# SCH_L2-P2_3.net
KiCad netlist of a schematic drawn in Altium Designer
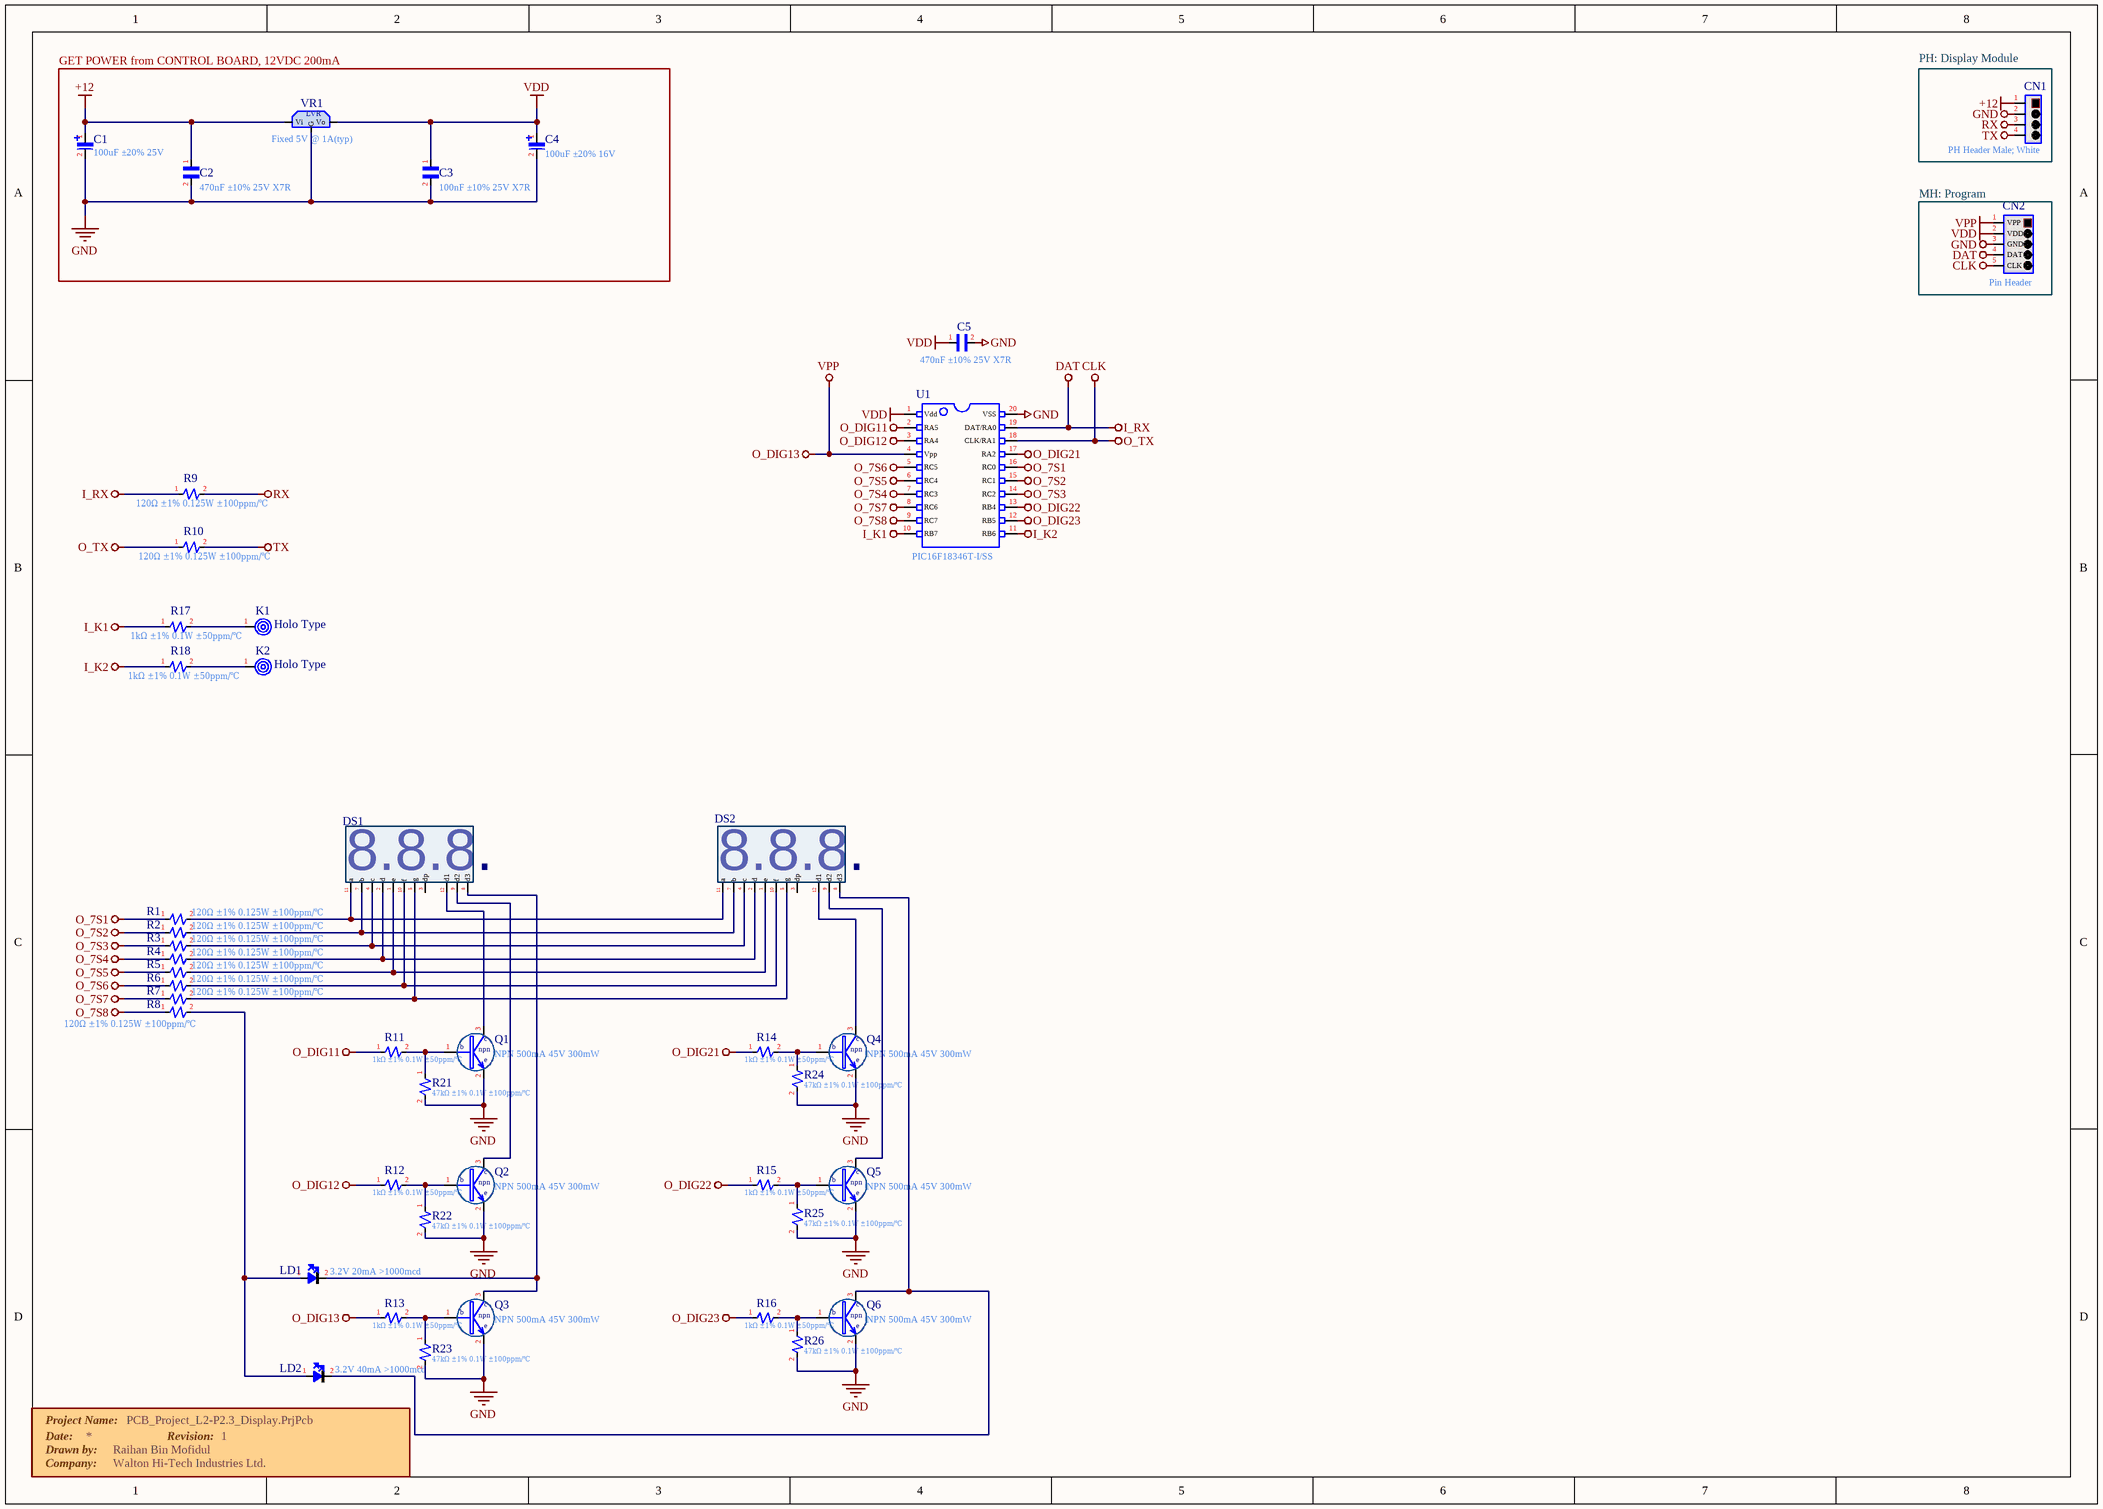
[diagram p0: SCH_L2-P2.3.SchDoc]

(export (version "E")
  (design (tool "Eeschema 10.0.6"))
  (components
    (comp (ref "C1")
      (value "100uF ±20% 25V")
      (footprint "C_SMD_Ø6.3*5.4mm")
      (description "SMD,6.3x5.4mm Aluminum Electrolytic Capacitors - SMD RoHS")
      (libsource (lib "RBM_ALTIUM_SCH_LIBRARY") (part "Capacitor{gt}{gt} Polar"))
    )
    (comp (ref "C2")
      (value "470nF ±10% 25V X7R")
      (footprint "C_0603")
      (description "0603 Multilayer Ceramic Capacitors MLCC - SMD/SMT RoHS")
      (libsource (lib "") (part "Capacitor{gt}{gt} Non-Polar_1"))
    )
    (comp (ref "C3")
      (value "100nF ±10% 25V X7R")
      (footprint "C_0603")
      (description "0603 Multilayer Ceramic Capacitors MLCC - SMD/SMT RoHS")
      (libsource (lib "") (part "Capacitor{gt}{gt} Non-Polar_1"))
    )
    (comp (ref "C4")
      (value "100uF ±20% 16V")
      (footprint "C_SMD_Ø6.3*5.4mm")
      (description "SMD,6.3x5.4mm Aluminum Electrolytic Capacitors - SMD RoHS")
      (libsource (lib "RBM_ALTIUM_SCH_LIBRARY") (part "Capacitor{gt}{gt} Polar"))
    )
    (comp (ref "C5")
      (value "470nF ±10% 25V X7R")
      (footprint "C_0603")
      (description "0603 Multilayer Ceramic Capacitors MLCC - SMD/SMT RoHS")
      (libsource (lib "RBM_ALTIUM_SCH_LIBRARY") (part "Capacitor{gt}{gt} Non-Polar"))
    )
    (comp (ref "CN1")
      (value "PH Header Male; White")
      (footprint "CN_4P_A2001WR-S-XP-LCP")
      (description "A2001WR-S-4P; Pin 0.079\"(2.00mm) 4 SMD,P=2mm Wire To Board / Wire To Wire Connector RoHS")
      (libsource (lib "RBM_ALTIUM_SCH_LIBRARY") (part "Connector{gt}{gt} 4Pins"))
    )
    (comp (ref "CN2")
      (value "Pin Header")
      (footprint "CN_PIC_MCU_Debugger_RightAngle")
      (libsource (lib "RBM_ALTIUM_SCH_LIBRARY") (part "Connector{gt}{gt} PIC Program"))
    )
    (comp (ref "DS1")
      (value "Display>> 7Seg 3Dig")
      (footprint "DS_0.36\"_3DIG")
      (libsource (lib "RBM_ALTIUM_SCH_LIBRARY") (part "Display{gt}{gt} 7Seg 3Dig"))
    )
    (comp (ref "DS2")
      (value "Display>> 7Seg 3Dig")
      (footprint "DS_0.36\"_3DIG")
      (libsource (lib "RBM_ALTIUM_SCH_LIBRARY") (part "Display{gt}{gt} 7Seg 3Dig"))
    )
    (comp (ref "K1")
      (value "Holo Type")
      (footprint "K_Cap-Touch-Square_LED")
      (libsource (lib "RBM_ALTIUM_SCH_LIBRARY") (part "Key{gt}{gt} Cap Touch"))
    )
    (comp (ref "K2")
      (value "Holo Type")
      (footprint "K_Cap-Touch-Square_LED")
      (libsource (lib "RBM_ALTIUM_SCH_LIBRARY") (part "Key{gt}{gt} Cap Touch"))
    )
    (comp (ref "LD1")
      (value "3.2V 20mA >1000mcd")
      (footprint "LED_4.8x5.8_P2.54")
      (libsource (lib "RBM_ALTIUM_SCH_LIBRARY") (part "LED{gt}{gt} General Purpose"))
    )
    (comp (ref "LD2")
      (value "3.2V 40mA >1000mcd")
      (footprint "LED_4.8x5.8_P2.54")
      (libsource (lib "RBM_ALTIUM_SCH_LIBRARY") (part "LED{gt}{gt} General Purpose"))
    )
    (comp (ref "Q1")
      (value "NPN 500mA 45V 300mW")
      (footprint "Q_SOT-23_NPN")
      (description "BC817-40; SOT-23(SOT-23-3) Transistors (NPN/PNP) RoHS")
      (libsource (lib "RBM_ALTIUM_SCH_LIBRARY") (part "Transistor{gt}{gt} BJT npn"))
    )
    (comp (ref "Q2")
      (value "NPN 500mA 45V 300mW")
      (footprint "Q_SOT-23_NPN")
      (description "BC817-40; SOT-23(SOT-23-3) Transistors (NPN/PNP) RoHS")
      (libsource (lib "RBM_ALTIUM_SCH_LIBRARY") (part "Transistor{gt}{gt} BJT npn"))
    )
    (comp (ref "Q3")
      (value "NPN 500mA 45V 300mW")
      (footprint "Q_SOT-23_NPN")
      (description "BC817-40; SOT-23(SOT-23-3) Transistors (NPN/PNP) RoHS")
      (libsource (lib "RBM_ALTIUM_SCH_LIBRARY") (part "Transistor{gt}{gt} BJT npn"))
    )
    (comp (ref "Q4")
      (value "NPN 500mA 45V 300mW")
      (footprint "Q_SOT-23_NPN")
      (description "BC817-40; SOT-23(SOT-23-3) Transistors (NPN/PNP) RoHS")
      (libsource (lib "RBM_ALTIUM_SCH_LIBRARY") (part "Transistor{gt}{gt} BJT npn"))
    )
    (comp (ref "Q5")
      (value "NPN 500mA 45V 300mW")
      (footprint "Q_SOT-23_NPN")
      (description "BC817-40; SOT-23(SOT-23-3) Transistors (NPN/PNP) RoHS")
      (libsource (lib "RBM_ALTIUM_SCH_LIBRARY") (part "Transistor{gt}{gt} BJT npn"))
    )
    (comp (ref "Q6")
      (value "NPN 500mA 45V 300mW")
      (footprint "Q_SOT-23_NPN")
      (description "BC817-40; SOT-23(SOT-23-3) Transistors (NPN/PNP) RoHS")
      (libsource (lib "RBM_ALTIUM_SCH_LIBRARY") (part "Transistor{gt}{gt} BJT npn"))
    )
    (comp (ref "R1")
      (value "120Ω ±1% 0.125W ±100ppm/℃")
      (footprint "R_0603")
      (description "RK73H1JTTD1200F; 0603 Chip Resistor - Surface Mount RoHS")
      (libsource (lib "RBM_ALTIUM_SCH_LIBRARY") (part "Resistor{gt}{gt} General Purpose"))
    )
    (comp (ref "R2")
      (value "120Ω ±1% 0.125W ±100ppm/℃")
      (footprint "R_0603")
      (description "RK73H1JTTD1200F; 0603 Chip Resistor - Surface Mount RoHS")
      (libsource (lib "RBM_ALTIUM_SCH_LIBRARY") (part "Resistor{gt}{gt} General Purpose"))
    )
    (comp (ref "R3")
      (value "120Ω ±1% 0.125W ±100ppm/℃")
      (footprint "R_0603")
      (description "RK73H1JTTD1200F; 0603 Chip Resistor - Surface Mount RoHS")
      (libsource (lib "RBM_ALTIUM_SCH_LIBRARY") (part "Resistor{gt}{gt} General Purpose"))
    )
    (comp (ref "R4")
      (value "120Ω ±1% 0.125W ±100ppm/℃")
      (footprint "R_0603")
      (description "RK73H1JTTD1200F; 0603 Chip Resistor - Surface Mount RoHS")
      (libsource (lib "RBM_ALTIUM_SCH_LIBRARY") (part "Resistor{gt}{gt} General Purpose"))
    )
    (comp (ref "R5")
      (value "120Ω ±1% 0.125W ±100ppm/℃")
      (footprint "R_0603")
      (description "RK73H1JTTD1200F; 0603 Chip Resistor - Surface Mount RoHS")
      (libsource (lib "RBM_ALTIUM_SCH_LIBRARY") (part "Resistor{gt}{gt} General Purpose"))
    )
    (comp (ref "R6")
      (value "120Ω ±1% 0.125W ±100ppm/℃")
      (footprint "R_0603")
      (description "RK73H1JTTD1200F; 0603 Chip Resistor - Surface Mount RoHS")
      (libsource (lib "RBM_ALTIUM_SCH_LIBRARY") (part "Resistor{gt}{gt} General Purpose"))
    )
    (comp (ref "R7")
      (value "120Ω ±1% 0.125W ±100ppm/℃")
      (footprint "R_0603")
      (description "RK73H1JTTD1200F; 0603 Chip Resistor - Surface Mount RoHS")
      (libsource (lib "RBM_ALTIUM_SCH_LIBRARY") (part "Resistor{gt}{gt} General Purpose"))
    )
    (comp (ref "R8")
      (value "120Ω ±1% 0.125W ±100ppm/℃")
      (footprint "R_0603")
      (description "RK73H1JTTD1200F; 0603 Chip Resistor - Surface Mount RoHS")
      (libsource (lib "RBM_ALTIUM_SCH_LIBRARY") (part "Resistor{gt}{gt} General Purpose"))
    )
    (comp (ref "R9")
      (value "120Ω ±1% 0.125W ±100ppm/℃")
      (footprint "R_0603")
      (description "RK73H1JTTD1200F; 0603 Chip Resistor - Surface Mount RoHS")
      (libsource (lib "RBM_ALTIUM_SCH_LIBRARY") (part "Resistor{gt}{gt} General Purpose"))
    )
    (comp (ref "R10")
      (value "120Ω ±1% 0.125W ±100ppm/℃")
      (footprint "R_0603")
      (description "RK73H1JTTD1200F; 0603 Chip Resistor - Surface Mount RoHS")
      (libsource (lib "RBM_ALTIUM_SCH_LIBRARY") (part "Resistor{gt}{gt} General Purpose"))
    )
    (comp (ref "R11")
      (value "1kΩ ±1% 0.1W ±50ppm/℃")
      (footprint "R_0603")
      (description "RK73G1JTTD1001F; 0603 Chip Resistor - Surface Mount RoHS")
      (libsource (lib "RBM_ALTIUM_SCH_LIBRARY") (part "Resistor{gt}{gt} General Purpose"))
    )
    (comp (ref "R12")
      (value "1kΩ ±1% 0.1W ±50ppm/℃")
      (footprint "R_0603")
      (description "RK73G1JTTD1001F; 0603 Chip Resistor - Surface Mount RoHS")
      (libsource (lib "RBM_ALTIUM_SCH_LIBRARY") (part "Resistor{gt}{gt} General Purpose"))
    )
    (comp (ref "R13")
      (value "1kΩ ±1% 0.1W ±50ppm/℃")
      (footprint "R_0603")
      (description "RK73G1JTTD1001F; 0603 Chip Resistor - Surface Mount RoHS")
      (libsource (lib "RBM_ALTIUM_SCH_LIBRARY") (part "Resistor{gt}{gt} General Purpose"))
    )
    (comp (ref "R14")
      (value "1kΩ ±1% 0.1W ±50ppm/℃")
      (footprint "R_0603")
      (description "RK73G1JTTD1001F; 0603 Chip Resistor - Surface Mount RoHS")
      (libsource (lib "RBM_ALTIUM_SCH_LIBRARY") (part "Resistor{gt}{gt} General Purpose"))
    )
    (comp (ref "R15")
      (value "1kΩ ±1% 0.1W ±50ppm/℃")
      (footprint "R_0603")
      (description "RK73G1JTTD1001F; 0603 Chip Resistor - Surface Mount RoHS")
      (libsource (lib "RBM_ALTIUM_SCH_LIBRARY") (part "Resistor{gt}{gt} General Purpose"))
    )
    (comp (ref "R16")
      (value "1kΩ ±1% 0.1W ±50ppm/℃")
      (footprint "R_0603")
      (description "RK73G1JTTD1001F; 0603 Chip Resistor - Surface Mount RoHS")
      (libsource (lib "RBM_ALTIUM_SCH_LIBRARY") (part "Resistor{gt}{gt} General Purpose"))
    )
    (comp (ref "R17")
      (value "1kΩ ±1% 0.1W ±50ppm/℃")
      (footprint "R_0603")
      (description "RK73G1JTTD1001F; 0603 Chip Resistor - Surface Mount RoHS")
      (libsource (lib "RBM_ALTIUM_SCH_LIBRARY") (part "Resistor{gt}{gt} General Purpose"))
    )
    (comp (ref "R18")
      (value "1kΩ ±1% 0.1W ±50ppm/℃")
      (footprint "R_0603")
      (description "RK73G1JTTD1001F; 0603 Chip Resistor - Surface Mount RoHS")
      (libsource (lib "RBM_ALTIUM_SCH_LIBRARY") (part "Resistor{gt}{gt} General Purpose"))
    )
    (comp (ref "R21")
      (value "47kΩ ±1% 0.1W ±100ppm/℃")
      (footprint "R_0603")
      (description "RK73H1JTTD4702F; 0603 Chip Resistor - Surface Mount RoHS")
      (libsource (lib "RBM_ALTIUM_SCH_LIBRARY") (part "Resistor{gt}{gt} General Purpose"))
    )
    (comp (ref "R22")
      (value "47kΩ ±1% 0.1W ±100ppm/℃")
      (footprint "R_0603")
      (description "RK73H1JTTD4702F; 0603 Chip Resistor - Surface Mount RoHS")
      (libsource (lib "RBM_ALTIUM_SCH_LIBRARY") (part "Resistor{gt}{gt} General Purpose"))
    )
    (comp (ref "R23")
      (value "47kΩ ±1% 0.1W ±100ppm/℃")
      (footprint "R_0603")
      (description "RK73H1JTTD4702F; 0603 Chip Resistor - Surface Mount RoHS")
      (libsource (lib "RBM_ALTIUM_SCH_LIBRARY") (part "Resistor{gt}{gt} General Purpose"))
    )
    (comp (ref "R24")
      (value "47kΩ ±1% 0.1W ±100ppm/℃")
      (footprint "R_0603")
      (description "RK73H1JTTD4702F; 0603 Chip Resistor - Surface Mount RoHS")
      (libsource (lib "RBM_ALTIUM_SCH_LIBRARY") (part "Resistor{gt}{gt} General Purpose"))
    )
    (comp (ref "R25")
      (value "47kΩ ±1% 0.1W ±100ppm/℃")
      (footprint "R_0603")
      (description "RK73H1JTTD4702F; 0603 Chip Resistor - Surface Mount RoHS")
      (libsource (lib "RBM_ALTIUM_SCH_LIBRARY") (part "Resistor{gt}{gt} General Purpose"))
    )
    (comp (ref "R26")
      (value "47kΩ ±1% 0.1W ±100ppm/℃")
      (footprint "R_0603")
      (description "RK73H1JTTD4702F; 0603 Chip Resistor - Surface Mount RoHS")
      (libsource (lib "RBM_ALTIUM_SCH_LIBRARY") (part "Resistor{gt}{gt} General Purpose"))
    )
    (comp (ref "U1")
      (value "PIC16F18346T-I/SS")
      (footprint "U_PIC_20pin_SSOP")
      (libsource (lib "RBM_ALTIUM_SCH_LIBRARY") (part "IC{gt}{gt} PIC 20Pins"))
    )
    (comp (ref "VR1")
      (value "Fixed 5V @ 1A(typ)")
      (footprint "VR_TO-252-2(DPAK)")
      (description "CJ78D05/MC7805BDTRKG; TO-252-2(DPAK) Dropout Regulators(LDO) RoHS")
      (libsource (lib "RBM_ALTIUM_SCH_LIBRARY") (part "Voltage Regulator"))
    )
  )
  (nets
    (net (code "1") (name "+12") (class "Default")
      (node (ref "C1") (pin "1") (pinfunction "1_1") (pintype "passive"))
      (node (ref "C2") (pin "1") (pinfunction "1_1") (pintype "passive"))
      (node (ref "CN1") (pin "1") (pinfunction "1_1") (pintype "passive"))
      (node (ref "VR1") (pin "V-IN") (pinfunction "Vi_V-IN") (pintype "passive"))
    )
    (net (code "2") (name "CLK") (class "Default")
      (node (ref "CN2") (pin "5") (pinfunction "CLK_5") (pintype "passive"))
      (node (ref "R10") (pin "1") (pinfunction "1_1") (pintype "passive"))
      (node (ref "U1") (pin "18") (pinfunction "CLK/RA1_18") (pintype "passive"))
    )
    (net (code "3") (name "DAT") (class "Default")
      (node (ref "CN2") (pin "4") (pinfunction "DAT_4") (pintype "passive"))
      (node (ref "R9") (pin "1") (pinfunction "1_1") (pintype "passive"))
      (node (ref "U1") (pin "19") (pinfunction "DAT/RA0_19") (pintype "passive"))
    )
    (net (code "4") (name "GND") (class "Default")
      (node (ref "C1") (pin "2") (pinfunction "2_2") (pintype "passive"))
      (node (ref "C2") (pin "2") (pinfunction "2_2") (pintype "passive"))
      (node (ref "C3") (pin "2") (pinfunction "2_2") (pintype "passive"))
      (node (ref "C4") (pin "2") (pinfunction "2_2") (pintype "passive"))
      (node (ref "C5") (pin "2") (pinfunction "2_2") (pintype "passive"))
      (node (ref "CN1") (pin "2") (pinfunction "2_2") (pintype "passive"))
      (node (ref "CN2") (pin "3") (pinfunction "GND_3") (pintype "passive"))
      (node (ref "Q1") (pin "2") (pinfunction "Emitter_2") (pintype "passive"))
      (node (ref "Q2") (pin "2") (pinfunction "Emitter_2") (pintype "passive"))
      (node (ref "Q3") (pin "2") (pinfunction "Emitter_2") (pintype "passive"))
      (node (ref "Q4") (pin "2") (pinfunction "Emitter_2") (pintype "passive"))
      (node (ref "Q5") (pin "2") (pinfunction "Emitter_2") (pintype "passive"))
      (node (ref "Q6") (pin "2") (pinfunction "Emitter_2") (pintype "passive"))
      (node (ref "R21") (pin "2") (pinfunction "2_2") (pintype "passive"))
      (node (ref "R22") (pin "2") (pinfunction "2_2") (pintype "passive"))
      (node (ref "R23") (pin "2") (pinfunction "2_2") (pintype "passive"))
      (node (ref "R24") (pin "2") (pinfunction "2_2") (pintype "passive"))
      (node (ref "R25") (pin "2") (pinfunction "2_2") (pintype "passive"))
      (node (ref "R26") (pin "2") (pinfunction "2_2") (pintype "passive"))
      (node (ref "U1") (pin "20") (pinfunction "VSS_20") (pintype "passive"))
      (node (ref "VR1") (pin "GND") (pinfunction "G_GND") (pintype "passive"))
    )
    (net (code "5") (name "I_K1") (class "Default")
      (node (ref "R17") (pin "1") (pinfunction "1_1") (pintype "passive"))
      (node (ref "U1") (pin "10") (pinfunction "RB7_10") (pintype "passive"))
    )
    (net (code "6") (name "I_K2") (class "Default")
      (node (ref "R18") (pin "1") (pinfunction "1_1") (pintype "passive"))
      (node (ref "U1") (pin "11") (pinfunction "RB6_11") (pintype "passive"))
    )
    (net (code "7") (name "Net-(DS1-a)") (class "Default")
      (node (ref "DS1") (pin "11") (pinfunction "a_11") (pintype "passive"))
      (node (ref "DS2") (pin "11") (pinfunction "a_11") (pintype "passive"))
      (node (ref "R1") (pin "2") (pinfunction "2_2") (pintype "passive"))
    )
    (net (code "8") (name "Net-(DS1-b)") (class "Default")
      (node (ref "DS1") (pin "7") (pinfunction "b_7") (pintype "passive"))
      (node (ref "DS2") (pin "7") (pinfunction "b_7") (pintype "passive"))
      (node (ref "R2") (pin "2") (pinfunction "2_2") (pintype "passive"))
    )
    (net (code "9") (name "Net-(DS1-c)") (class "Default")
      (node (ref "DS1") (pin "4") (pinfunction "c_4") (pintype "passive"))
      (node (ref "DS2") (pin "4") (pinfunction "c_4") (pintype "passive"))
      (node (ref "R3") (pin "2") (pinfunction "2_2") (pintype "passive"))
    )
    (net (code "10") (name "Net-(DS1-d)") (class "Default")
      (node (ref "DS1") (pin "2") (pinfunction "d_2") (pintype "passive"))
      (node (ref "DS2") (pin "2") (pinfunction "d_2") (pintype "passive"))
      (node (ref "R4") (pin "2") (pinfunction "2_2") (pintype "passive"))
    )
    (net (code "11") (name "Net-(DS1-d1)") (class "Default")
      (node (ref "DS1") (pin "12") (pinfunction "d1_12") (pintype "passive"))
      (node (ref "Q1") (pin "3") (pinfunction "Collector_3") (pintype "passive"))
    )
    (net (code "12") (name "Net-(DS1-d2)") (class "Default")
      (node (ref "DS1") (pin "9") (pinfunction "d2_9") (pintype "passive"))
      (node (ref "Q2") (pin "3") (pinfunction "Collector_3") (pintype "passive"))
    )
    (net (code "13") (name "Net-(DS1-d3)") (class "Default")
      (node (ref "DS1") (pin "8") (pinfunction "d3_8") (pintype "passive"))
      (node (ref "LD1") (pin "2") (pinfunction "vss_2") (pintype "passive"))
      (node (ref "Q3") (pin "3") (pinfunction "Collector_3") (pintype "passive"))
    )
    (net (code "14") (name "Net-(DS1-e)") (class "Default")
      (node (ref "DS1") (pin "1") (pinfunction "e_1") (pintype "passive"))
      (node (ref "DS2") (pin "1") (pinfunction "e_1") (pintype "passive"))
      (node (ref "R5") (pin "2") (pinfunction "2_2") (pintype "passive"))
    )
    (net (code "15") (name "Net-(DS1-f)") (class "Default")
      (node (ref "DS1") (pin "10") (pinfunction "f_10") (pintype "passive"))
      (node (ref "DS2") (pin "10") (pinfunction "f_10") (pintype "passive"))
      (node (ref "R6") (pin "2") (pinfunction "2_2") (pintype "passive"))
    )
    (net (code "16") (name "Net-(DS1-g)") (class "Default")
      (node (ref "DS1") (pin "5") (pinfunction "g_5") (pintype "passive"))
      (node (ref "DS2") (pin "5") (pinfunction "g_5") (pintype "passive"))
      (node (ref "R7") (pin "2") (pinfunction "2_2") (pintype "passive"))
    )
    (net (code "17") (name "Net-(DS2-d1)") (class "Default")
      (node (ref "DS2") (pin "12") (pinfunction "d1_12") (pintype "passive"))
      (node (ref "Q4") (pin "3") (pinfunction "Collector_3") (pintype "passive"))
    )
    (net (code "18") (name "Net-(DS2-d2)") (class "Default")
      (node (ref "DS2") (pin "9") (pinfunction "d2_9") (pintype "passive"))
      (node (ref "Q5") (pin "3") (pinfunction "Collector_3") (pintype "passive"))
    )
    (net (code "19") (name "Net-(DS2-d3)") (class "Default")
      (node (ref "DS2") (pin "8") (pinfunction "d3_8") (pintype "passive"))
      (node (ref "LD2") (pin "2") (pinfunction "vss_2") (pintype "passive"))
      (node (ref "Q6") (pin "3") (pinfunction "Collector_3") (pintype "passive"))
    )
    (net (code "20") (name "Net-(K1-Pad1)") (class "Default")
      (node (ref "K1") (pin "1") (pinfunction "1_1") (pintype "passive"))
      (node (ref "R17") (pin "2") (pinfunction "2_2") (pintype "passive"))
    )
    (net (code "21") (name "Net-(K2-Pad1)") (class "Default")
      (node (ref "K2") (pin "1") (pinfunction "1_1") (pintype "passive"))
      (node (ref "R18") (pin "2") (pinfunction "2_2") (pintype "passive"))
    )
    (net (code "22") (name "Net-(LD1-vdd)") (class "Default")
      (node (ref "LD1") (pin "1") (pinfunction "vdd_1") (pintype "passive"))
      (node (ref "LD2") (pin "1") (pinfunction "vdd_1") (pintype "passive"))
      (node (ref "R8") (pin "2") (pinfunction "2_2") (pintype "passive"))
    )
    (net (code "23") (name "Net-(Q1-Base)") (class "Default")
      (node (ref "Q1") (pin "1") (pinfunction "Base_1") (pintype "passive"))
      (node (ref "R11") (pin "2") (pinfunction "2_2") (pintype "passive"))
      (node (ref "R21") (pin "1") (pinfunction "1_1") (pintype "passive"))
    )
    (net (code "24") (name "Net-(Q2-Base)") (class "Default")
      (node (ref "Q2") (pin "1") (pinfunction "Base_1") (pintype "passive"))
      (node (ref "R12") (pin "2") (pinfunction "2_2") (pintype "passive"))
      (node (ref "R22") (pin "1") (pinfunction "1_1") (pintype "passive"))
    )
    (net (code "25") (name "Net-(Q3-Base)") (class "Default")
      (node (ref "Q3") (pin "1") (pinfunction "Base_1") (pintype "passive"))
      (node (ref "R13") (pin "2") (pinfunction "2_2") (pintype "passive"))
      (node (ref "R23") (pin "1") (pinfunction "1_1") (pintype "passive"))
    )
    (net (code "26") (name "Net-(Q4-Base)") (class "Default")
      (node (ref "Q4") (pin "1") (pinfunction "Base_1") (pintype "passive"))
      (node (ref "R14") (pin "2") (pinfunction "2_2") (pintype "passive"))
      (node (ref "R24") (pin "1") (pinfunction "1_1") (pintype "passive"))
    )
    (net (code "27") (name "Net-(Q5-Base)") (class "Default")
      (node (ref "Q5") (pin "1") (pinfunction "Base_1") (pintype "passive"))
      (node (ref "R15") (pin "2") (pinfunction "2_2") (pintype "passive"))
      (node (ref "R25") (pin "1") (pinfunction "1_1") (pintype "passive"))
    )
    (net (code "28") (name "Net-(Q6-Base)") (class "Default")
      (node (ref "Q6") (pin "1") (pinfunction "Base_1") (pintype "passive"))
      (node (ref "R16") (pin "2") (pinfunction "2_2") (pintype "passive"))
      (node (ref "R26") (pin "1") (pinfunction "1_1") (pintype "passive"))
    )
    (net (code "29") (name "O_7S1") (class "Default")
      (node (ref "R1") (pin "1") (pinfunction "1_1") (pintype "passive"))
      (node (ref "U1") (pin "16") (pinfunction "RC0_16") (pintype "passive"))
    )
    (net (code "30") (name "O_7S2") (class "Default")
      (node (ref "R2") (pin "1") (pinfunction "1_1") (pintype "passive"))
      (node (ref "U1") (pin "15") (pinfunction "RC1_15") (pintype "passive"))
    )
    (net (code "31") (name "O_7S3") (class "Default")
      (node (ref "R3") (pin "1") (pinfunction "1_1") (pintype "passive"))
      (node (ref "U1") (pin "14") (pinfunction "RC2_14") (pintype "passive"))
    )
    (net (code "32") (name "O_7S4") (class "Default")
      (node (ref "R4") (pin "1") (pinfunction "1_1") (pintype "passive"))
      (node (ref "U1") (pin "7") (pinfunction "RC3_7") (pintype "passive"))
    )
    (net (code "33") (name "O_7S5") (class "Default")
      (node (ref "R5") (pin "1") (pinfunction "1_1") (pintype "passive"))
      (node (ref "U1") (pin "6") (pinfunction "RC4_6") (pintype "passive"))
    )
    (net (code "34") (name "O_7S6") (class "Default")
      (node (ref "R6") (pin "1") (pinfunction "1_1") (pintype "passive"))
      (node (ref "U1") (pin "5") (pinfunction "RC5_5") (pintype "passive"))
    )
    (net (code "35") (name "O_7S7") (class "Default")
      (node (ref "R7") (pin "1") (pinfunction "1_1") (pintype "passive"))
      (node (ref "U1") (pin "8") (pinfunction "RC6_8") (pintype "passive"))
    )
    (net (code "36") (name "O_7S8") (class "Default")
      (node (ref "R8") (pin "1") (pinfunction "1_1") (pintype "passive"))
      (node (ref "U1") (pin "9") (pinfunction "RC7_9") (pintype "passive"))
    )
    (net (code "37") (name "O_DIG11") (class "Default")
      (node (ref "R11") (pin "1") (pinfunction "1_1") (pintype "passive"))
      (node (ref "U1") (pin "2") (pinfunction "RA5_2") (pintype "passive"))
    )
    (net (code "38") (name "O_DIG12") (class "Default")
      (node (ref "R12") (pin "1") (pinfunction "1_1") (pintype "passive"))
      (node (ref "U1") (pin "3") (pinfunction "RA4_3") (pintype "passive"))
    )
    (net (code "39") (name "O_DIG13") (class "Default")
      (node (ref "CN2") (pin "1") (pinfunction "VPP_1") (pintype "passive"))
      (node (ref "R13") (pin "1") (pinfunction "1_1") (pintype "passive"))
      (node (ref "U1") (pin "4") (pinfunction "Vpp_4") (pintype "passive"))
    )
    (net (code "40") (name "O_DIG21") (class "Default")
      (node (ref "R14") (pin "1") (pinfunction "1_1") (pintype "passive"))
      (node (ref "U1") (pin "17") (pinfunction "RA2_17") (pintype "passive"))
    )
    (net (code "41") (name "O_DIG22") (class "Default")
      (node (ref "R15") (pin "1") (pinfunction "1_1") (pintype "passive"))
      (node (ref "U1") (pin "13") (pinfunction "RB4_13") (pintype "passive"))
    )
    (net (code "42") (name "O_DIG23") (class "Default")
      (node (ref "R16") (pin "1") (pinfunction "1_1") (pintype "passive"))
      (node (ref "U1") (pin "12") (pinfunction "RB5_12") (pintype "passive"))
    )
    (net (code "43") (name "RX") (class "Default")
      (node (ref "CN1") (pin "3") (pinfunction "3_3") (pintype "passive"))
      (node (ref "R9") (pin "2") (pinfunction "2_2") (pintype "passive"))
    )
    (net (code "44") (name "TX") (class "Default")
      (node (ref "CN1") (pin "4") (pinfunction "4_4") (pintype "passive"))
      (node (ref "R10") (pin "2") (pinfunction "2_2") (pintype "passive"))
    )
    (net (code "45") (name "VDD") (class "Default")
      (node (ref "C3") (pin "1") (pinfunction "1_1") (pintype "passive"))
      (node (ref "C4") (pin "1") (pinfunction "1_1") (pintype "passive"))
      (node (ref "C5") (pin "1") (pinfunction "1_1") (pintype "passive"))
      (node (ref "CN2") (pin "2") (pinfunction "VDD_2") (pintype "passive"))
      (node (ref "U1") (pin "1") (pinfunction "Vdd_1") (pintype "passive"))
      (node (ref "VR1") (pin "V-OUT") (pinfunction "Vo_V-OUT") (pintype "passive"))
    )
    (net (code "46") (name "unconnected-(DS1-dp-Pad3)") (class "Default")
      (node (ref "DS1") (pin "3") (pinfunction "dp_3") (pintype "passive"))
    )
    (net (code "47") (name "unconnected-(DS2-dp-Pad3)") (class "Default")
      (node (ref "DS2") (pin "3") (pinfunction "dp_3") (pintype "passive"))
    )
  )
)
